# extpower.net
KiCad netlist of a schematic drawn in EAGLE
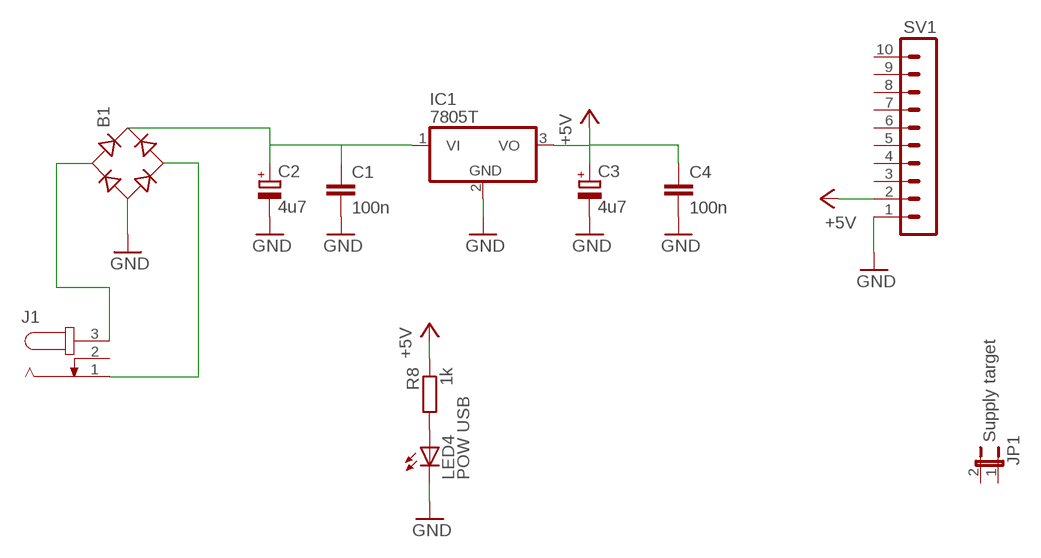
[diagram p0: schematic, sheet 1]

(export (version "E")
  (design (tool "Eeschema 10.0.6"))
  (components
    (comp (ref "B1")
      (value "RB1A")
      (footprint "eagle-import:RB1A")
      (libsource (lib "eagle-import") (part "RB1A"))
    )
    (comp (ref "C1")
      (value "100n")
      (footprint "eagle-import:C025-024X044")
      (libsource (lib "eagle-import") (part "C-EU025-024X044"))
    )
    (comp (ref "C2")
      (value "4u7")
      (footprint "eagle-import:TT2D5")
      (libsource (lib "eagle-import") (part "CPOL-EUTT2D5"))
    )
    (comp (ref "C3")
      (value "4u7")
      (footprint "eagle-import:TT2D5")
      (libsource (lib "eagle-import") (part "CPOL-EUTT2D5"))
    )
    (comp (ref "C4")
      (value "100n")
      (footprint "eagle-import:C025-024X044")
      (libsource (lib "eagle-import") (part "C-EU025-024X044"))
    )
    (comp (ref "IC1")
      (value "7805T")
      (footprint "eagle-import:TO220H")
      (libsource (lib "eagle-import") (part "78T05"))
    )
    (comp (ref "J1")
      (value "JACK-PLUG0")
      (footprint "eagle-import:SPC4077")
      (libsource (lib "eagle-import") (part "JACK-PLUG0"))
    )
    (comp (ref "JP1")
      (value "Supply target")
      (footprint "eagle-import:JP1")
      (libsource (lib "eagle-import") (part "JP1E"))
    )
    (comp (ref "LED4")
      (value "POW USB")
      (footprint "eagle-import:LED3MM")
      (libsource (lib "eagle-import") (part "LED3MM"))
    )
    (comp (ref "R8")
      (value "1k")
      (footprint "eagle-import:0207_10")
      (libsource (lib "eagle-import") (part "R-EU_0207/10"))
    )
    (comp (ref "SV1")
      (value "MA10-1W")
      (footprint "eagle-import:MA10-1W")
      (libsource (lib "eagle-import") (part "MA10-1W"))
    )
  )
  (nets
    (net (code "1") (name "+5V") (class "Default")
      (node (ref "C3") (pin "+") (pinfunction "+_+") (pintype "passive"))
      (node (ref "C4") (pin "1") (pinfunction "1_1") (pintype "passive"))
      (node (ref "IC1") (pin "3") (pinfunction "VO_3") (pintype "passive"))
      (node (ref "R8") (pin "1") (pinfunction "1_1") (pintype "passive"))
      (node (ref "SV1") (pin "2") (pinfunction "2_2") (pintype "passive"))
    )
    (net (code "2") (name "GND") (class "Default")
      (node (ref "B1") (pin "-") (pinfunction "-_-") (pintype "passive"))
      (node (ref "C1") (pin "2") (pinfunction "2_2") (pintype "passive"))
      (node (ref "C2") (pin "-") (pinfunction "-_-") (pintype "passive"))
      (node (ref "C3") (pin "-") (pinfunction "-_-") (pintype "passive"))
      (node (ref "C4") (pin "2") (pinfunction "2_2") (pintype "passive"))
      (node (ref "IC1") (pin "2") (pinfunction "GND_2") (pintype "passive"))
      (node (ref "LED4") (pin "K") (pinfunction "C_K") (pintype "passive"))
      (node (ref "SV1") (pin "1") (pinfunction "1_1") (pintype "passive"))
    )
    (net (code "3") (name "Net-(B1-PadAC1)") (class "Default")
      (node (ref "B1") (pin "AC1") (pinfunction "AC1_AC1") (pintype "passive"))
      (node (ref "J1") (pin "3") (pinfunction "3_3") (pintype "passive"))
    )
    (net (code "4") (name "Net-(B1-PadAC2)") (class "Default")
      (node (ref "B1") (pin "AC2") (pinfunction "AC2_AC2") (pintype "passive"))
      (node (ref "J1") (pin "1") (pinfunction "1_1") (pintype "passive"))
    )
    (net (code "5") (name "Net-(IC1-VI)") (class "Default")
      (node (ref "B1") (pin "+") (pinfunction "+_+") (pintype "passive"))
      (node (ref "C1") (pin "1") (pinfunction "1_1") (pintype "passive"))
      (node (ref "C2") (pin "+") (pinfunction "+_+") (pintype "passive"))
      (node (ref "IC1") (pin "1") (pinfunction "VI_1") (pintype "input"))
    )
    (net (code "6") (name "Net-(LED4-PadA)") (class "Default")
      (node (ref "LED4") (pin "A") (pinfunction "A_A") (pintype "passive"))
      (node (ref "R8") (pin "2") (pinfunction "2_2") (pintype "passive"))
    )
    (net (code "7") (name "unconnected-(J1-Pad2)") (class "Default")
      (node (ref "J1") (pin "2") (pinfunction "2_2") (pintype "passive"))
    )
    (net (code "8") (name "unconnected-(JP1-Pad1)") (class "Default")
      (node (ref "JP1") (pin "1") (pinfunction "1_1") (pintype "passive"))
    )
    (net (code "9") (name "unconnected-(JP1-Pad2)") (class "Default")
      (node (ref "JP1") (pin "2") (pinfunction "2_2") (pintype "passive"))
    )
    (net (code "10") (name "unconnected-(SV1-Pad3)") (class "Default")
      (node (ref "SV1") (pin "3") (pinfunction "3_3") (pintype "passive"))
    )
    (net (code "11") (name "unconnected-(SV1-Pad4)") (class "Default")
      (node (ref "SV1") (pin "4") (pinfunction "4_4") (pintype "passive"))
    )
    (net (code "12") (name "unconnected-(SV1-Pad5)") (class "Default")
      (node (ref "SV1") (pin "5") (pinfunction "5_5") (pintype "passive"))
    )
    (net (code "13") (name "unconnected-(SV1-Pad6)") (class "Default")
      (node (ref "SV1") (pin "6") (pinfunction "6_6") (pintype "passive"))
    )
    (net (code "14") (name "unconnected-(SV1-Pad7)") (class "Default")
      (node (ref "SV1") (pin "7") (pinfunction "7_7") (pintype "passive"))
    )
    (net (code "15") (name "unconnected-(SV1-Pad8)") (class "Default")
      (node (ref "SV1") (pin "8") (pinfunction "8_8") (pintype "passive"))
    )
    (net (code "16") (name "unconnected-(SV1-Pad9)") (class "Default")
      (node (ref "SV1") (pin "9") (pinfunction "9_9") (pintype "passive"))
    )
    (net (code "17") (name "unconnected-(SV1-Pad10)") (class "Default")
      (node (ref "SV1") (pin "10") (pinfunction "10_10") (pintype "passive"))
    )
  )
)
